# I2C_Messenger_r1.net
KiCad netlist of a schematic drawn in EAGLE
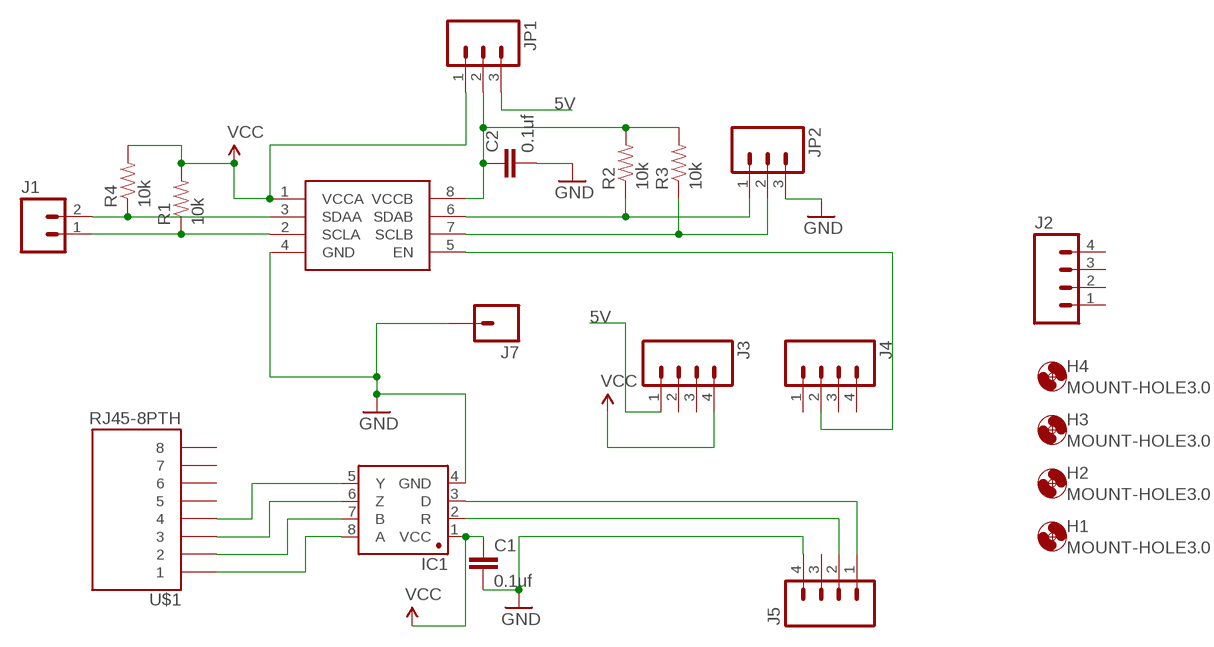
[diagram p0: schematic, sheet 1]

(export (version "E")
  (design (tool "Eeschema 10.0.6"))
  (components
    (comp (ref "C1")
      (value "0.1uf")
      (footprint "eagle-import:1206")
      (libsource (lib "eagle-import") (part "CAP1206"))
    )
    (comp (ref "C2")
      (value "0.1uf")
      (footprint "eagle-import:1206")
      (libsource (lib "eagle-import") (part "CAP1206"))
    )
    (comp (ref "H1")
      (value "MOUNT-HOLE3.0")
      (footprint "eagle-import:3,0")
      (libsource (lib "eagle-import") (part "MOUNT-HOLE3.0"))
    )
    (comp (ref "H2")
      (value "MOUNT-HOLE3.0")
      (footprint "eagle-import:3,0")
      (libsource (lib "eagle-import") (part "MOUNT-HOLE3.0"))
    )
    (comp (ref "H3")
      (value "MOUNT-HOLE3.0")
      (footprint "eagle-import:3,0")
      (libsource (lib "eagle-import") (part "MOUNT-HOLE3.0"))
    )
    (comp (ref "H4")
      (value "MOUNT-HOLE3.0")
      (footprint "eagle-import:3,0")
      (libsource (lib "eagle-import") (part "MOUNT-HOLE3.0"))
    )
    (comp (ref "IC1")
      (value "SN65HVD31DR")
      (footprint "eagle-import:SO08")
      (libsource (lib "eagle-import") (part "SN65HVD31DR"))
    )
    (comp (ref "IC2")
      (value "PCA9517")
      (footprint "eagle-import:SO-08")
      (libsource (lib "eagle-import") (part "PCA9517"))
    )
    (comp (ref "J1")
      (value "M02PTH")
      (footprint "eagle-import:1X02")
      (libsource (lib "eagle-import") (part "M02PTH"))
    )
    (comp (ref "J2")
      (value "M04PTH")
      (footprint "eagle-import:1X04")
      (libsource (lib "eagle-import") (part "M04PTH"))
    )
    (comp (ref "J3")
      (value "M04PTH")
      (footprint "eagle-import:1X04")
      (libsource (lib "eagle-import") (part "M04PTH"))
    )
    (comp (ref "J4")
      (value "M04PTH")
      (footprint "eagle-import:1X04")
      (libsource (lib "eagle-import") (part "M04PTH"))
    )
    (comp (ref "J5")
      (value "M04PTH")
      (footprint "eagle-import:1X04")
      (libsource (lib "eagle-import") (part "M04PTH"))
    )
    (comp (ref "J7")
      (value "M01PTH")
      (footprint "eagle-import:1X01")
      (libsource (lib "eagle-import") (part "M01PTH"))
    )
    (comp (ref "JP1")
      (value "M03PTH")
      (footprint "eagle-import:1X03")
      (libsource (lib "eagle-import") (part "M03PTH"))
    )
    (comp (ref "JP2")
      (value "M03SCREW_LOCK")
      (footprint "eagle-import:SCREWTERMINAL-3.5MM-3_LOCK.007S")
      (libsource (lib "eagle-import") (part "M03SCREW_LOCK"))
    )
    (comp (ref "R1")
      (value "10k")
      (footprint "eagle-import:1206")
      (libsource (lib "eagle-import") (part "RESISTOR1206"))
    )
    (comp (ref "R2")
      (value "10k")
      (footprint "eagle-import:1206")
      (libsource (lib "eagle-import") (part "RESISTOR1206"))
    )
    (comp (ref "R3")
      (value "10k")
      (footprint "eagle-import:1206")
      (libsource (lib "eagle-import") (part "RESISTOR1206"))
    )
    (comp (ref "R4")
      (value "10k")
      (footprint "eagle-import:1206")
      (libsource (lib "eagle-import") (part "RESISTOR1206"))
    )
    (comp (ref "U$1")
      (value "RJ45-8PTH")
      (footprint "eagle-import:RJ45-8")
      (libsource (lib "eagle-import") (part "RJ45-8PTH"))
    )
  )
  (nets
    (net (code "1") (name "/5V") (class "Default")
      (node (ref "J3") (pin "1") (pinfunction "1_1") (pintype "passive"))
      (node (ref "JP1") (pin "3") (pinfunction "3_3") (pintype "passive"))
    )
    (net (code "2") (name "GND") (class "Default")
      (node (ref "C1") (pin "2") (pinfunction "2_2") (pintype "passive"))
      (node (ref "C2") (pin "2") (pinfunction "2_2") (pintype "passive"))
      (node (ref "IC1") (pin "4") (pinfunction "GND_4") (pintype "bidirectional"))
      (node (ref "IC2") (pin "4") (pinfunction "GND_4") (pintype "bidirectional"))
      (node (ref "J5") (pin "4") (pinfunction "4_4") (pintype "passive"))
      (node (ref "J7") (pin "1") (pinfunction "1_1") (pintype "passive"))
      (node (ref "JP2") (pin "3") (pinfunction "3_3") (pintype "passive"))
    )
    (net (code "3") (name "Net-(IC1-A)") (class "Default")
      (node (ref "IC1") (pin "8") (pinfunction "A_8") (pintype "bidirectional"))
      (node (ref "U$1") (pin "1") (pinfunction "1_1") (pintype "bidirectional"))
    )
    (net (code "4") (name "Net-(IC1-B)") (class "Default")
      (node (ref "IC1") (pin "7") (pinfunction "B_7") (pintype "bidirectional"))
      (node (ref "U$1") (pin "2") (pinfunction "2_2") (pintype "bidirectional"))
    )
    (net (code "5") (name "Net-(IC1-D)") (class "Default")
      (node (ref "IC1") (pin "3") (pinfunction "D_3") (pintype "bidirectional"))
      (node (ref "J5") (pin "1") (pinfunction "1_1") (pintype "passive"))
    )
    (net (code "6") (name "Net-(IC1-R)") (class "Default")
      (node (ref "IC1") (pin "2") (pinfunction "R_2") (pintype "bidirectional"))
      (node (ref "J5") (pin "2") (pinfunction "2_2") (pintype "passive"))
    )
    (net (code "7") (name "Net-(IC1-Y)") (class "Default")
      (node (ref "IC1") (pin "5") (pinfunction "Y_5") (pintype "bidirectional"))
      (node (ref "U$1") (pin "4") (pinfunction "4_4") (pintype "bidirectional"))
    )
    (net (code "8") (name "Net-(IC1-Z)") (class "Default")
      (node (ref "IC1") (pin "6") (pinfunction "Z_6") (pintype "bidirectional"))
      (node (ref "U$1") (pin "3") (pinfunction "3_3") (pintype "bidirectional"))
    )
    (net (code "9") (name "Net-(IC2-EN)") (class "Default")
      (node (ref "IC2") (pin "5") (pinfunction "EN_5") (pintype "bidirectional"))
      (node (ref "J4") (pin "2") (pinfunction "2_2") (pintype "passive"))
    )
    (net (code "10") (name "Net-(IC2-SCLA)") (class "Default")
      (node (ref "IC2") (pin "2") (pinfunction "SCLA_2") (pintype "bidirectional"))
      (node (ref "J1") (pin "1") (pinfunction "1_1") (pintype "passive"))
      (node (ref "R1") (pin "1") (pinfunction "1_1") (pintype "passive"))
    )
    (net (code "11") (name "Net-(IC2-SCLB)") (class "Default")
      (node (ref "IC2") (pin "7") (pinfunction "SCLB_7") (pintype "bidirectional"))
      (node (ref "JP2") (pin "2") (pinfunction "2_2") (pintype "passive"))
      (node (ref "R3") (pin "1") (pinfunction "1_1") (pintype "passive"))
    )
    (net (code "12") (name "Net-(IC2-SDAA)") (class "Default")
      (node (ref "IC2") (pin "3") (pinfunction "SDAA_3") (pintype "bidirectional"))
      (node (ref "J1") (pin "2") (pinfunction "2_2") (pintype "passive"))
      (node (ref "R4") (pin "1") (pinfunction "1_1") (pintype "passive"))
    )
    (net (code "13") (name "Net-(IC2-SDAB)") (class "Default")
      (node (ref "IC2") (pin "6") (pinfunction "SDAB_6") (pintype "bidirectional"))
      (node (ref "JP2") (pin "1") (pinfunction "1_1") (pintype "passive"))
      (node (ref "R2") (pin "1") (pinfunction "1_1") (pintype "passive"))
    )
    (net (code "14") (name "Net-(IC2-VCCB)") (class "Default")
      (node (ref "C2") (pin "1") (pinfunction "1_1") (pintype "passive"))
      (node (ref "IC2") (pin "8") (pinfunction "VCCB_8") (pintype "bidirectional"))
      (node (ref "JP1") (pin "2") (pinfunction "2_2") (pintype "passive"))
      (node (ref "R2") (pin "2") (pinfunction "2_2") (pintype "passive"))
      (node (ref "R3") (pin "2") (pinfunction "2_2") (pintype "passive"))
    )
    (net (code "15") (name "VCC") (class "Default")
      (node (ref "C1") (pin "1") (pinfunction "1_1") (pintype "passive"))
      (node (ref "IC1") (pin "1") (pinfunction "VCC_1") (pintype "bidirectional"))
      (node (ref "IC2") (pin "1") (pinfunction "VCCA_1") (pintype "bidirectional"))
      (node (ref "J3") (pin "4") (pinfunction "4_4") (pintype "passive"))
      (node (ref "JP1") (pin "1") (pinfunction "1_1") (pintype "passive"))
      (node (ref "R1") (pin "2") (pinfunction "2_2") (pintype "passive"))
      (node (ref "R4") (pin "2") (pinfunction "2_2") (pintype "passive"))
    )
    (net (code "16") (name "unconnected-(J2-Pad1)") (class "Default")
      (node (ref "J2") (pin "1") (pinfunction "1_1") (pintype "passive"))
    )
    (net (code "17") (name "unconnected-(J2-Pad2)") (class "Default")
      (node (ref "J2") (pin "2") (pinfunction "2_2") (pintype "passive"))
    )
    (net (code "18") (name "unconnected-(J2-Pad3)") (class "Default")
      (node (ref "J2") (pin "3") (pinfunction "3_3") (pintype "passive"))
    )
    (net (code "19") (name "unconnected-(J2-Pad4)") (class "Default")
      (node (ref "J2") (pin "4") (pinfunction "4_4") (pintype "passive"))
    )
    (net (code "20") (name "unconnected-(J3-Pad2)") (class "Default")
      (node (ref "J3") (pin "2") (pinfunction "2_2") (pintype "passive"))
    )
    (net (code "21") (name "unconnected-(J3-Pad3)") (class "Default")
      (node (ref "J3") (pin "3") (pinfunction "3_3") (pintype "passive"))
    )
    (net (code "22") (name "unconnected-(J4-Pad1)") (class "Default")
      (node (ref "J4") (pin "1") (pinfunction "1_1") (pintype "passive"))
    )
    (net (code "23") (name "unconnected-(J4-Pad3)") (class "Default")
      (node (ref "J4") (pin "3") (pinfunction "3_3") (pintype "passive"))
    )
    (net (code "24") (name "unconnected-(J4-Pad4)") (class "Default")
      (node (ref "J4") (pin "4") (pinfunction "4_4") (pintype "passive"))
    )
    (net (code "25") (name "unconnected-(J5-Pad3)") (class "Default")
      (node (ref "J5") (pin "3") (pinfunction "3_3") (pintype "passive"))
    )
    (net (code "26") (name "unconnected-(U$1-Pad5)") (class "Default")
      (node (ref "U$1") (pin "5") (pinfunction "5_5") (pintype "bidirectional"))
    )
    (net (code "27") (name "unconnected-(U$1-Pad6)") (class "Default")
      (node (ref "U$1") (pin "6") (pinfunction "6_6") (pintype "bidirectional"))
    )
    (net (code "28") (name "unconnected-(U$1-Pad7)") (class "Default")
      (node (ref "U$1") (pin "7") (pinfunction "7_7") (pintype "bidirectional"))
    )
    (net (code "29") (name "unconnected-(U$1-Pad8)") (class "Default")
      (node (ref "U$1") (pin "8") (pinfunction "8_8") (pintype "bidirectional"))
    )
  )
)
